# PixiFlood_1_7_PTH.net
KiCad netlist of a schematic drawn in EAGLE
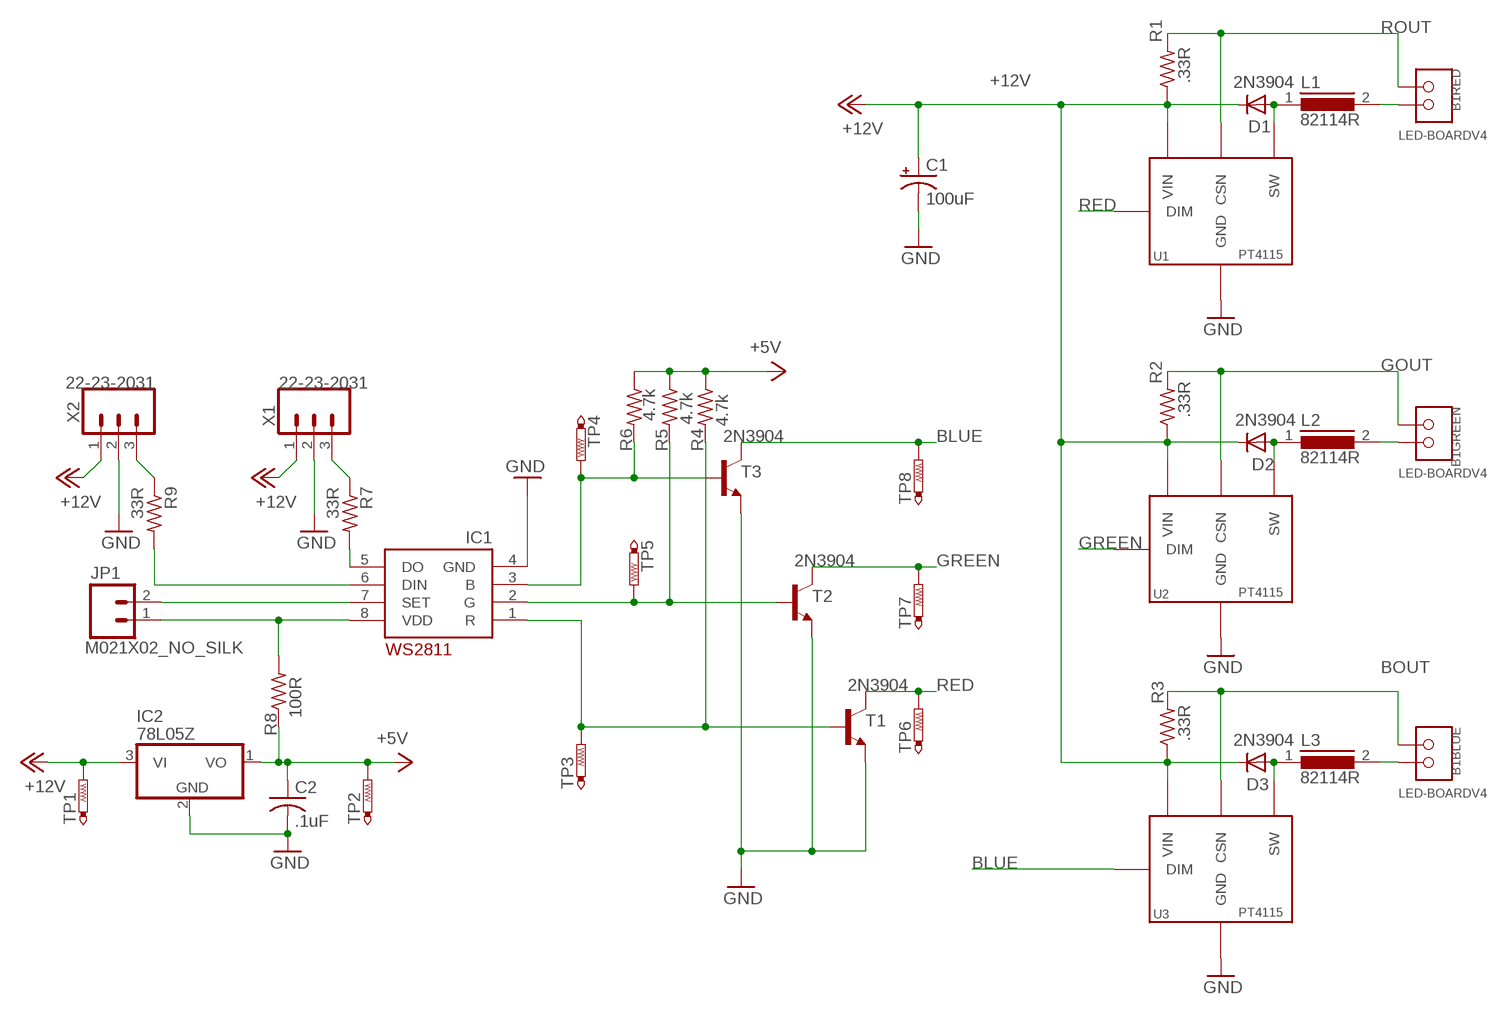
[diagram p0: schematic, sheet 1]

(export (version "E")
  (design (tool "Eeschema 10.0.6"))
  (components
    (comp (ref "B1")
      (value "LED-BOARDV4")
      (footprint "eagle-import:LED_BOARD-V4")
      (libsource (lib "eagle-import") (part "LED-BOARDV4"))
    )
    (comp (ref "C1")
      (value "100uF")
      (footprint "eagle-import:TT2D6L")
      (libsource (lib "eagle-import") (part "CPOL-USTT2D6L"))
    )
    (comp (ref "C2")
      (value ".1uF")
      (footprint "eagle-import:C050-024X044")
      (libsource (lib "eagle-import") (part "C-US050-024X044"))
    )
    (comp (ref "D1")
      (value "2N3904")
      (footprint "eagle-import:DO07")
      (libsource (lib "eagle-import") (part "DIODE-DO07"))
    )
    (comp (ref "D2")
      (value "2N3904")
      (footprint "eagle-import:DO07")
      (libsource (lib "eagle-import") (part "DIODE-DO07"))
    )
    (comp (ref "D3")
      (value "2N3904")
      (footprint "eagle-import:DO07")
      (libsource (lib "eagle-import") (part "DIODE-DO07"))
    )
    (comp (ref "IC1")
      (value "WS2811-SOP8")
      (footprint "eagle-import:SO08-SKINNYPADS")
      (libsource (lib "eagle-import") (part "WS2811-SOP8"))
    )
    (comp (ref "IC2")
      (value "78L05Z")
      (footprint "eagle-import:TO92")
      (libsource (lib "eagle-import") (part "78ZL05"))
    )
    (comp (ref "JP1")
      (value "M021X02_NO_SILK")
      (footprint "eagle-import:1X02_NO_SILK")
      (libsource (lib "eagle-import") (part "M021X02_NO_SILK"))
    )
    (comp (ref "L1")
      (value "82114R")
      (footprint "eagle-import:82114R")
      (libsource (lib "eagle-import") (part "82114R"))
    )
    (comp (ref "L2")
      (value "82114R")
      (footprint "eagle-import:82114R")
      (libsource (lib "eagle-import") (part "82114R"))
    )
    (comp (ref "L3")
      (value "82114R")
      (footprint "eagle-import:82114R")
      (libsource (lib "eagle-import") (part "82114R"))
    )
    (comp (ref "R1")
      (value ".33R")
      (footprint "eagle-import:0204_7")
      (libsource (lib "eagle-import") (part "resistor_R-US_0204/7"))
    )
    (comp (ref "R2")
      (value ".33R")
      (footprint "eagle-import:0204_7")
      (libsource (lib "eagle-import") (part "resistor_R-US_0204/7"))
    )
    (comp (ref "R3")
      (value ".33R")
      (footprint "eagle-import:0204_7")
      (libsource (lib "eagle-import") (part "resistor_R-US_0204/7"))
    )
    (comp (ref "R4")
      (value "4.7k")
      (footprint "eagle-import:0204_7")
      (libsource (lib "eagle-import") (part "resistor_R-US_0204/7"))
    )
    (comp (ref "R5")
      (value "4.7k")
      (footprint "eagle-import:0204_7")
      (libsource (lib "eagle-import") (part "resistor_R-US_0204/7"))
    )
    (comp (ref "R6")
      (value "4.7k")
      (footprint "eagle-import:0204_7")
      (libsource (lib "eagle-import") (part "resistor_R-US_0204/7"))
    )
    (comp (ref "R7")
      (value "33R")
      (footprint "eagle-import:0204_7")
      (libsource (lib "eagle-import") (part "R-US_0204/7"))
    )
    (comp (ref "R8")
      (value "100R")
      (footprint "eagle-import:0204_7")
      (libsource (lib "eagle-import") (part "R-US_0204/7"))
    )
    (comp (ref "R9")
      (value "33R")
      (footprint "eagle-import:0204_7")
      (libsource (lib "eagle-import") (part "R-US_0204/7"))
    )
    (comp (ref "T1")
      (value "2N3904")
      (footprint "eagle-import:TO92")
      (libsource (lib "eagle-import") (part "2N3904"))
    )
    (comp (ref "T2")
      (value "2N3904")
      (footprint "eagle-import:TO92")
      (libsource (lib "eagle-import") (part "2N3904"))
    )
    (comp (ref "T3")
      (value "2N3904")
      (footprint "eagle-import:TO92")
      (libsource (lib "eagle-import") (part "2N3904"))
    )
    (comp (ref "TP1")
      (value "PTR1B2,54")
      (footprint "eagle-import:B2,54")
      (libsource (lib "eagle-import") (part "PTR1B2,54"))
    )
    (comp (ref "TP2")
      (value "PTR1B2,54")
      (footprint "eagle-import:B2,54")
      (libsource (lib "eagle-import") (part "PTR1B2,54"))
    )
    (comp (ref "TP3")
      (value "PTR1B1,27")
      (footprint "eagle-import:B1,27")
      (libsource (lib "eagle-import") (part "PTR1B1,27"))
    )
    (comp (ref "TP4")
      (value "PTR1B1,27")
      (footprint "eagle-import:B1,27")
      (libsource (lib "eagle-import") (part "PTR1B1,27"))
    )
    (comp (ref "TP5")
      (value "PTR1B1,27")
      (footprint "eagle-import:B1,27")
      (libsource (lib "eagle-import") (part "PTR1B1,27"))
    )
    (comp (ref "TP6")
      (value "PTR1B1,27")
      (footprint "eagle-import:B1,27")
      (libsource (lib "eagle-import") (part "PTR1B1,27"))
    )
    (comp (ref "TP7")
      (value "PTR1B1,27")
      (footprint "eagle-import:B1,27")
      (libsource (lib "eagle-import") (part "PTR1B1,27"))
    )
    (comp (ref "TP8")
      (value "PTR1B1,27")
      (footprint "eagle-import:B1,27")
      (libsource (lib "eagle-import") (part "PTR1B1,27"))
    )
    (comp (ref "U1")
      (value "PT4115B89E")
      (footprint "eagle-import:SOT89-5")
      (libsource (lib "eagle-import") (part "PT4115B89E"))
    )
    (comp (ref "U2")
      (value "PT4115B89E")
      (footprint "eagle-import:SOT89-5")
      (libsource (lib "eagle-import") (part "PT4115B89E"))
    )
    (comp (ref "U3")
      (value "PT4115B89E")
      (footprint "eagle-import:SOT89-5")
      (libsource (lib "eagle-import") (part "PT4115B89E"))
    )
    (comp (ref "X1")
      (value "22-23-2031")
      (footprint "eagle-import:22-23-2031")
      (fields (field (name "MF") "MOLEX"))
      (libsource (lib "eagle-import") (part "22-23-2031"))
    )
    (comp (ref "X2")
      (value "22-23-2031")
      (footprint "eagle-import:22-23-2031")
      (fields (field (name "MF") "MOLEX"))
      (libsource (lib "eagle-import") (part "22-23-2031"))
    )
  )
  (nets
    (net (code "1") (name "+5V") (class "Default")
      (node (ref "C2") (pin "1") (pinfunction "1_1") (pintype "passive"))
      (node (ref "IC2") (pin "1") (pinfunction "VO_1") (pintype "passive"))
      (node (ref "R4") (pin "1") (pinfunction "1_1") (pintype "passive"))
      (node (ref "R5") (pin "1") (pinfunction "1_1") (pintype "passive"))
      (node (ref "R6") (pin "1") (pinfunction "1_1") (pintype "passive"))
      (node (ref "R8") (pin "1") (pinfunction "1_1") (pintype "passive"))
      (node (ref "TP2") (pin "TP") (pinfunction "TP_TP") (pintype "input"))
    )
    (net (code "2") (name "+12V") (class "Default")
      (node (ref "C1") (pin "+") (pinfunction "+_+") (pintype "passive"))
      (node (ref "D1") (pin "C") (pinfunction "C_C") (pintype "passive"))
      (node (ref "D2") (pin "C") (pinfunction "C_C") (pintype "passive"))
      (node (ref "D3") (pin "C") (pinfunction "C_C") (pintype "passive"))
      (node (ref "IC2") (pin "3") (pinfunction "VI_3") (pintype "input"))
      (node (ref "R1") (pin "1") (pinfunction "1_1") (pintype "passive"))
      (node (ref "R2") (pin "1") (pinfunction "1_1") (pintype "passive"))
      (node (ref "R3") (pin "1") (pinfunction "1_1") (pintype "passive"))
      (node (ref "TP1") (pin "TP") (pinfunction "TP_TP") (pintype "input"))
      (node (ref "U1") (pin "5") (pinfunction "VIN_5") (pintype "power_in"))
      (node (ref "U2") (pin "5") (pinfunction "VIN_5") (pintype "power_in"))
      (node (ref "U3") (pin "5") (pinfunction "VIN_5") (pintype "power_in"))
      (node (ref "X1") (pin "1") (pinfunction "1_1") (pintype "passive"))
      (node (ref "X2") (pin "1") (pinfunction "1_1") (pintype "passive"))
    )
    (net (code "3") (name "/BLUE") (class "Default")
      (node (ref "T3") (pin "1") (pinfunction "C_1") (pintype "passive"))
      (node (ref "TP8") (pin "TP") (pinfunction "TP_TP") (pintype "input"))
      (node (ref "U3") (pin "3") (pinfunction "DIM_3") (pintype "bidirectional"))
    )
    (net (code "4") (name "/BOUT") (class "Default")
      (node (ref "B1") (pin "B+") (pinfunction "P$2_B+") (pintype "bidirectional"))
      (node (ref "B1") (pin "B+@2") (pinfunction "P$2_B+@2") (pintype "bidirectional"))
      (node (ref "R3") (pin "2") (pinfunction "2_2") (pintype "passive"))
      (node (ref "U3") (pin "4") (pinfunction "CSN_4") (pintype "bidirectional"))
    )
    (net (code "5") (name "/GOUT") (class "Default")
      (node (ref "B1") (pin "G+") (pinfunction "P$2_G+") (pintype "bidirectional"))
      (node (ref "B1") (pin "G+@1") (pinfunction "P$2_G+@1") (pintype "bidirectional"))
      (node (ref "R2") (pin "2") (pinfunction "2_2") (pintype "passive"))
      (node (ref "U2") (pin "4") (pinfunction "CSN_4") (pintype "bidirectional"))
    )
    (net (code "6") (name "/GREEN") (class "Default")
      (node (ref "T2") (pin "1") (pinfunction "C_1") (pintype "passive"))
      (node (ref "TP7") (pin "TP") (pinfunction "TP_TP") (pintype "input"))
      (node (ref "U2") (pin "3") (pinfunction "DIM_3") (pintype "bidirectional"))
    )
    (net (code "7") (name "/RED") (class "Default")
      (node (ref "T1") (pin "1") (pinfunction "C_1") (pintype "passive"))
      (node (ref "TP6") (pin "TP") (pinfunction "TP_TP") (pintype "input"))
      (node (ref "U1") (pin "3") (pinfunction "DIM_3") (pintype "bidirectional"))
    )
    (net (code "8") (name "/ROUT") (class "Default")
      (node (ref "B1") (pin "R+") (pinfunction "P$2_R+") (pintype "bidirectional"))
      (node (ref "B1") (pin "R+@1") (pinfunction "P$2_R+@1") (pintype "bidirectional"))
      (node (ref "R1") (pin "2") (pinfunction "2_2") (pintype "passive"))
      (node (ref "U1") (pin "4") (pinfunction "CSN_4") (pintype "bidirectional"))
    )
    (net (code "9") (name "GND") (class "Default")
      (node (ref "C1") (pin "-") (pinfunction "-_-") (pintype "passive"))
      (node (ref "C2") (pin "2") (pinfunction "2_2") (pintype "passive"))
      (node (ref "IC1") (pin "4") (pinfunction "GND_4") (pintype "power_in"))
      (node (ref "IC2") (pin "2") (pinfunction "GND_2") (pintype "passive"))
      (node (ref "T1") (pin "3") (pinfunction "E_3") (pintype "passive"))
      (node (ref "T2") (pin "3") (pinfunction "E_3") (pintype "passive"))
      (node (ref "T3") (pin "3") (pinfunction "E_3") (pintype "passive"))
      (node (ref "U1") (pin "2") (pinfunction "GND_2") (pintype "power_in"))
      (node (ref "U1") (pin "2A") (pinfunction "GND_2A") (pintype "power_in"))
      (node (ref "U1") (pin "2A@1") (pinfunction "GND_2A@1") (pintype "power_in"))
      (node (ref "U1") (pin "2A@2") (pinfunction "GND_2A@2") (pintype "power_in"))
      (node (ref "U1") (pin "2A@3") (pinfunction "GND_2A@3") (pintype "power_in"))
      (node (ref "U1") (pin "2A@4") (pinfunction "GND_2A@4") (pintype "power_in"))
      (node (ref "U2") (pin "2") (pinfunction "GND_2") (pintype "power_in"))
      (node (ref "U2") (pin "2A") (pinfunction "GND_2A") (pintype "power_in"))
      (node (ref "U2") (pin "2A@1") (pinfunction "GND_2A@1") (pintype "power_in"))
      (node (ref "U2") (pin "2A@2") (pinfunction "GND_2A@2") (pintype "power_in"))
      (node (ref "U2") (pin "2A@3") (pinfunction "GND_2A@3") (pintype "power_in"))
      (node (ref "U2") (pin "2A@4") (pinfunction "GND_2A@4") (pintype "power_in"))
      (node (ref "U3") (pin "2") (pinfunction "GND_2") (pintype "power_in"))
      (node (ref "U3") (pin "2A") (pinfunction "GND_2A") (pintype "power_in"))
      (node (ref "U3") (pin "2A@1") (pinfunction "GND_2A@1") (pintype "power_in"))
      (node (ref "U3") (pin "2A@2") (pinfunction "GND_2A@2") (pintype "power_in"))
      (node (ref "U3") (pin "2A@3") (pinfunction "GND_2A@3") (pintype "power_in"))
      (node (ref "U3") (pin "2A@4") (pinfunction "GND_2A@4") (pintype "power_in"))
      (node (ref "X1") (pin "2") (pinfunction "2_2") (pintype "passive"))
      (node (ref "X2") (pin "2") (pinfunction "2_2") (pintype "passive"))
    )
    (net (code "10") (name "Net-(B1A-P$1-PadB-)") (class "Default")
      (node (ref "B1") (pin "B-") (pinfunction "P$1_B-") (pintype "bidirectional"))
      (node (ref "B1") (pin "B-@1") (pinfunction "P$1_B-@1") (pintype "bidirectional"))
      (node (ref "L3") (pin "2") (pinfunction "2_2") (pintype "passive"))
    )
    (net (code "11") (name "Net-(B1B-P$1-PadG-)") (class "Default")
      (node (ref "B1") (pin "G-") (pinfunction "P$1_G-") (pintype "bidirectional"))
      (node (ref "B1") (pin "G-@1") (pinfunction "P$1_G-@1") (pintype "bidirectional"))
      (node (ref "L2") (pin "2") (pinfunction "2_2") (pintype "passive"))
    )
    (net (code "12") (name "Net-(B1C-P$1-PadR-)") (class "Default")
      (node (ref "B1") (pin "R-") (pinfunction "P$1_R-") (pintype "bidirectional"))
      (node (ref "B1") (pin "R-@1") (pinfunction "P$1_R-@1") (pintype "bidirectional"))
      (node (ref "L1") (pin "2") (pinfunction "2_2") (pintype "passive"))
    )
    (net (code "13") (name "Net-(IC1-B)") (class "Default")
      (node (ref "IC1") (pin "3") (pinfunction "B_3") (pintype "open_collector"))
      (node (ref "R6") (pin "2") (pinfunction "2_2") (pintype "passive"))
      (node (ref "T3") (pin "2") (pinfunction "B_2") (pintype "passive"))
      (node (ref "TP4") (pin "TP") (pinfunction "TP_TP") (pintype "input"))
    )
    (net (code "14") (name "Net-(IC1-DIN)") (class "Default")
      (node (ref "IC1") (pin "6") (pinfunction "DIN_6") (pintype "input"))
      (node (ref "R9") (pin "2") (pinfunction "2_2") (pintype "passive"))
    )
    (net (code "15") (name "Net-(IC1-DO)") (class "Default")
      (node (ref "IC1") (pin "5") (pinfunction "DO_5") (pintype "output"))
      (node (ref "R7") (pin "2") (pinfunction "2_2") (pintype "passive"))
    )
    (net (code "16") (name "Net-(IC1-G)") (class "Default")
      (node (ref "IC1") (pin "2") (pinfunction "G_2") (pintype "open_collector"))
      (node (ref "R5") (pin "2") (pinfunction "2_2") (pintype "passive"))
      (node (ref "T2") (pin "2") (pinfunction "B_2") (pintype "passive"))
      (node (ref "TP5") (pin "TP") (pinfunction "TP_TP") (pintype "input"))
    )
    (net (code "17") (name "Net-(IC1-R)") (class "Default")
      (node (ref "IC1") (pin "1") (pinfunction "R_1") (pintype "open_collector"))
      (node (ref "R4") (pin "2") (pinfunction "2_2") (pintype "passive"))
      (node (ref "T1") (pin "2") (pinfunction "B_2") (pintype "passive"))
      (node (ref "TP3") (pin "TP") (pinfunction "TP_TP") (pintype "input"))
    )
    (net (code "18") (name "Net-(IC1-SET)") (class "Default")
      (node (ref "IC1") (pin "7") (pinfunction "SET_7") (pintype "input"))
      (node (ref "JP1") (pin "2") (pinfunction "2_2") (pintype "passive"))
    )
    (net (code "19") (name "Net-(IC1-VDD)") (class "Default")
      (node (ref "IC1") (pin "8") (pinfunction "VDD_8") (pintype "power_in"))
      (node (ref "JP1") (pin "1") (pinfunction "1_1") (pintype "passive"))
      (node (ref "R8") (pin "2") (pinfunction "2_2") (pintype "passive"))
    )
    (net (code "20") (name "Net-(R7-Pad1)") (class "Default")
      (node (ref "R7") (pin "1") (pinfunction "1_1") (pintype "passive"))
      (node (ref "X1") (pin "3") (pinfunction "3_3") (pintype "passive"))
    )
    (net (code "21") (name "Net-(R9-Pad1)") (class "Default")
      (node (ref "R9") (pin "1") (pinfunction "1_1") (pintype "passive"))
      (node (ref "X2") (pin "3") (pinfunction "3_3") (pintype "passive"))
    )
    (net (code "22") (name "Net-(U1-SW)") (class "Default")
      (node (ref "D1") (pin "A") (pinfunction "A_A") (pintype "passive"))
      (node (ref "L1") (pin "1") (pinfunction "1_1") (pintype "passive"))
      (node (ref "U1") (pin "1") (pinfunction "SW_1") (pintype "bidirectional"))
    )
    (net (code "23") (name "Net-(U2-SW)") (class "Default")
      (node (ref "D2") (pin "A") (pinfunction "A_A") (pintype "passive"))
      (node (ref "L2") (pin "1") (pinfunction "1_1") (pintype "passive"))
      (node (ref "U2") (pin "1") (pinfunction "SW_1") (pintype "bidirectional"))
    )
    (net (code "24") (name "Net-(U3-SW)") (class "Default")
      (node (ref "D3") (pin "A") (pinfunction "A_A") (pintype "passive"))
      (node (ref "L3") (pin "1") (pinfunction "1_1") (pintype "passive"))
      (node (ref "U3") (pin "1") (pinfunction "SW_1") (pintype "bidirectional"))
    )
  )
)
